# OMODRI_EtherCAT_1.net
KiCad netlist of a schematic drawn in Altium Designer
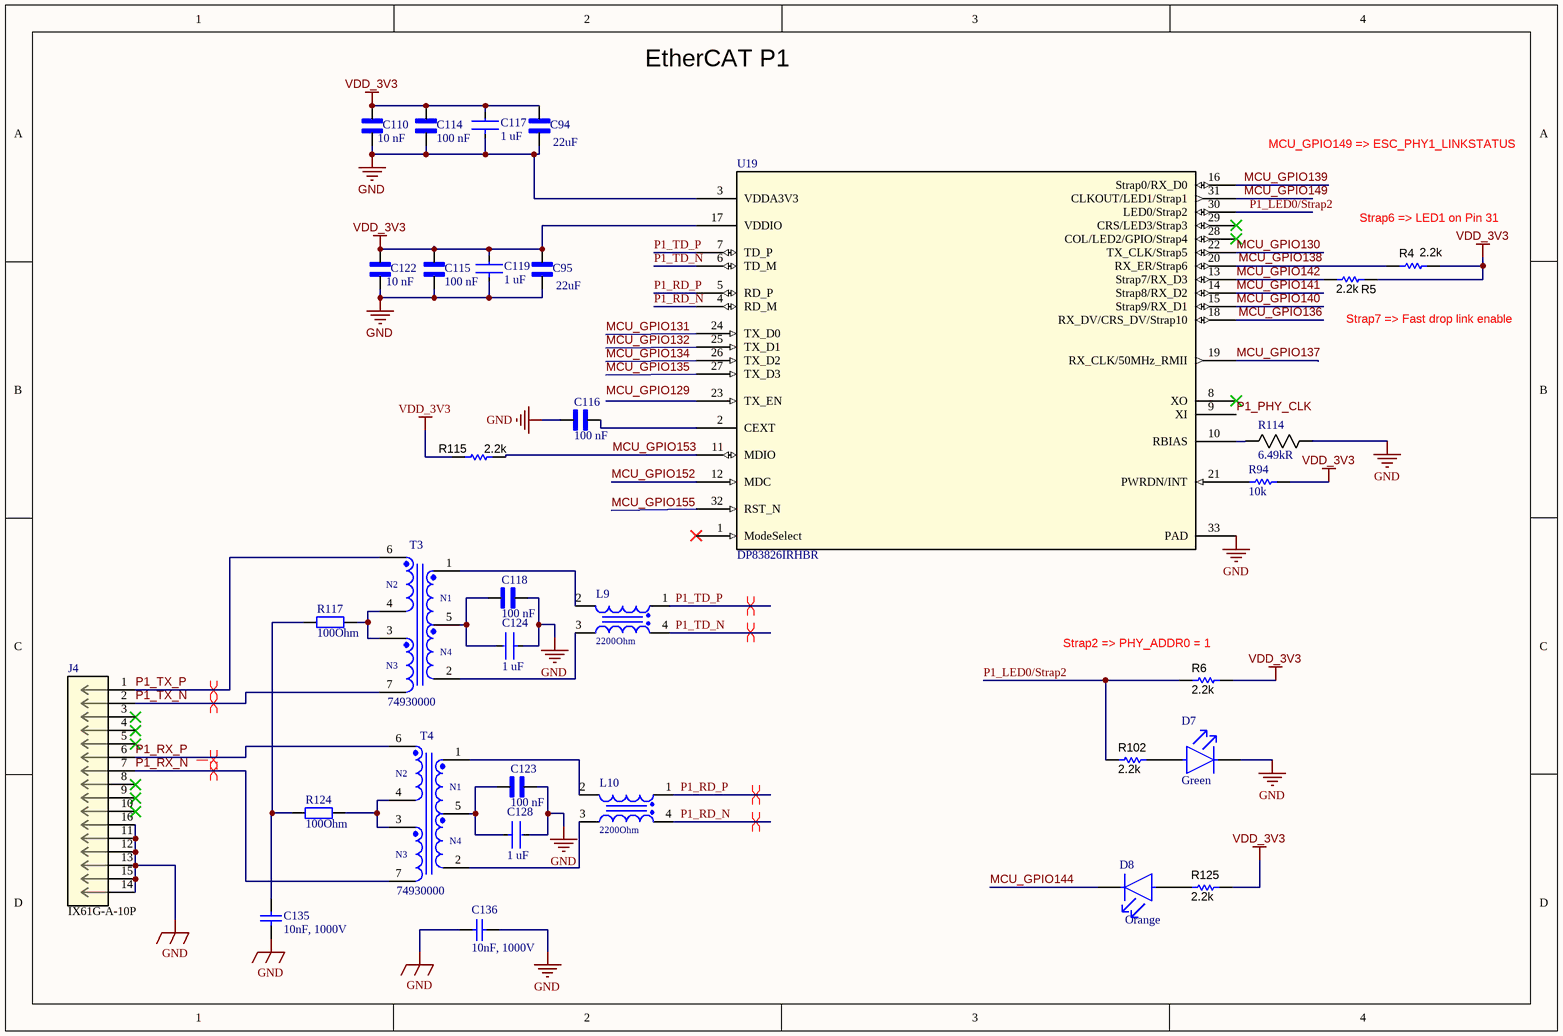
[diagram p0: OMODRI_EtherCAT_1.SchDoc]

(export (version "E")
  (design (tool "Eeschema 10.0.6"))
  (components
    (comp (ref "C94")
      (value "22uF")
      (footprint "CAPC1005X55N")
      (description "22µF ±20% 6.3V Ceramic Capacitor X5R 0402 (1005 Metric)")
      (fields (field (name "MP") "CL05A226MQ5N6J8") (field (name "MF") "Samsung Electro-Mechanics"))
      (libsource (lib "CL05A226MQ5N6J8") (part "CL05A226MQ5N6J8"))
    )
    (comp (ref "C95")
      (value "22uF")
      (footprint "CAPC1005X55N")
      (description "22µF ±20% 6.3V Ceramic Capacitor X5R 0402 (1005 Metric)")
      (fields (field (name "MP") "CL05A226MQ5N6J8") (field (name "MF") "Samsung Electro-Mechanics"))
      (libsource (lib "CL05A226MQ5N6J8") (part "CL05A226MQ5N6J8"))
    )
    (comp (ref "C110")
      (value "10 nF")
      (footprint "CAPC0603X33N")
      (description "SMD Capacitor X7R_EIA_ with Capacitance: 10000pF Tol. 10%. Rated Voltage: 25Vdc")
      (fields (field (name "MP") "GRM033R71E103KE14D") (field (name "MF") "Murata"))
      (libsource (lib "GRM033R71E103KE14D") (part "GRM033R71E103KE14D"))
    )
    (comp (ref "C114")
      (value "100 nF")
      (footprint "CAPC0603X33N")
      (description "SMD Capacitor X5R_EIA_ with Capacitance: 0.10uF Tol. 10%. Rated Voltage: 25Vdc")
      (fields (field (name "MF") "Murata") (field (name "MP") "GRM033R61E104KE14D"))
      (libsource (lib "") (part "GRM033R61E104KE14D_1"))
    )
    (comp (ref "C115")
      (value "100 nF")
      (footprint "CAPC0603X33N")
      (description "SMD Capacitor X5R_EIA_ with Capacitance: 0.10uF Tol. 10%. Rated Voltage: 25Vdc")
      (fields (field (name "MF") "Murata") (field (name "MP") "GRM033R61E104KE14D"))
      (libsource (lib "") (part "GRM033R61E104KE14D_1"))
    )
    (comp (ref "C116")
      (value "100 nF")
      (footprint "CAPC0603X33N")
      (description "SMD Capacitor X5R_EIA_ with Capacitance: 0.10uF Tol. 10%. Rated Voltage: 25Vdc")
      (fields (field (name "MF") "Murata") (field (name "MP") "GRM033R61E104KE14D"))
      (libsource (lib "GRM033R61E104KE14D") (part "GRM033R61E104KE14D"))
    )
    (comp (ref "C117")
      (value "1 uF")
      (footprint "FP-CC0201-BA-MFG")
      (description "CAP CER 1UF 6.3V X5R 0201")
      (fields (field (name "TOLERANCE") "0.2") (field (name "MANUFACTURER") "Yageo"))
      (libsource (lib "Altium Content Vault") (part "11868f565c42a9108669ba33697ecf6"))
    )
    (comp (ref "C118")
      (value "100 nF")
      (footprint "CAPC0603X33N")
      (description "SMD Capacitor X5R_EIA_ with Capacitance: 0.10uF Tol. 10%. Rated Voltage: 25Vdc")
      (fields (field (name "MF") "Murata") (field (name "MP") "GRM033R61E104KE14D"))
      (libsource (lib "GRM033R61E104KE14D") (part "GRM033R61E104KE14D"))
    )
    (comp (ref "C119")
      (value "1 uF")
      (footprint "FP-CC0201-BA-MFG")
      (description "CAP CER 1UF 6.3V X5R 0201")
      (fields (field (name "TOLERANCE") "0.2") (field (name "MANUFACTURER") "Yageo"))
      (libsource (lib "Altium Content Vault") (part "11868f565c42a9108669ba33697ecf6"))
    )
    (comp (ref "C122")
      (value "10 nF")
      (footprint "CAPC0603X33N")
      (description "SMD Capacitor X7R_EIA_ with Capacitance: 10000pF Tol. 10%. Rated Voltage: 25Vdc")
      (fields (field (name "MP") "GRM033R71E103KE14D") (field (name "MF") "Murata"))
      (libsource (lib "GRM033R71E103KE14D") (part "GRM033R71E103KE14D"))
    )
    (comp (ref "C123")
      (value "100 nF")
      (footprint "CAPC0603X33N")
      (description "SMD Capacitor X5R_EIA_ with Capacitance: 0.10uF Tol. 10%. Rated Voltage: 25Vdc")
      (fields (field (name "MF") "Murata") (field (name "MP") "GRM033R61E104KE14D"))
      (libsource (lib "GRM033R61E104KE14D") (part "GRM033R61E104KE14D"))
    )
    (comp (ref "C124")
      (value "1 uF")
      (footprint "FP-CC0201-BA-MFG")
      (description "CAP CER 1UF 6.3V X5R 0201")
      (fields (field (name "TOLERANCE") "0.2") (field (name "MANUFACTURER") "Yageo"))
      (libsource (lib "Altium Content Vault") (part "11868f565c42a9108669ba33697ecf6"))
    )
    (comp (ref "C128")
      (value "1 uF")
      (footprint "FP-CC0201-BA-MFG")
      (description "CAP CER 1UF 6.3V X5R 0201")
      (fields (field (name "TOLERANCE") "0.2") (field (name "MANUFACTURER") "Yageo"))
      (libsource (lib "Altium Content Vault") (part "11868f565c42a9108669ba33697ecf6"))
    )
    (comp (ref "C135")
      (value "10nF, 1000V")
      (footprint "WCAP-CSMH_1206_H=1.25mm")
      (description "WCAP-CSMH Ceramic Capacitors, size 1206, 10nF, 1000VDC")
      (fields (field (name "PART NUMBER") "885342208021") (field (name "PUBLISHER") "Wurth Elektronik"))
      (libsource (lib "WCAP-CSMH_1206") (part "885342208021"))
    )
    (comp (ref "C136")
      (value "10nF, 1000V")
      (footprint "WCAP-CSMH_1206_H=1.25mm")
      (description "WCAP-CSMH Ceramic Capacitors, size 1206, 10nF, 1000VDC")
      (fields (field (name "PART NUMBER") "885342208021") (field (name "PUBLISHER") "Wurth Elektronik"))
      (libsource (lib "WCAP-CSMH_1206") (part "885342208021"))
    )
    (comp (ref "D7")
      (value "SML-P11MTT86R")
      (footprint "ROHM-SML-P11MT_V")
      (description "LED Uni-Color Yellow Green 2-Pin Chip 0402(1006Metric) T/R")
      (fields
        (field (name "MANUFACTURER") "Rohm")
        (field (name "MANUFACTURER PART NUMBER") "SML-P11MTT86")
        (field (name "ILLUMINATION COLOR") "Green")
      )
      (libsource (lib "LED") (part "SML-P11MTT86R"))
    )
    (comp (ref "D8")
      (value "SML-P11DTT86R")
      (footprint "ROHM-SML-P11MT_V")
      (description "LED ORANGE CLEAR 1006 SMD")
      (fields (field (name "MANUFACTURER") "Rohm") (field (name "COLOR") "Orange"))
      (libsource (lib "LED") (part "SML-P11DTT86R"))
    )
    (comp (ref "J4")
      (value "Part Number: IX61G-A-10P")
      (footprint "CONN_1G-A-10P")
      (description "Conn Ethernet Connector RCP 10 POS Solder RA Thru-Hole 10 Terminal 1 Port Cat 5e/Cat 6a Reel")
      (fields
        (field (name "MANUFACTURER_PART_NUMBER") "IX61G-A-10P")
        (field (name "MANUFACTURER") "Hirose")
        (field (name "MANUFACTURER PART NUMBER") "IX61G-A-10P")
        (field (name "COPYRIGHT") "Copyright (C) 2018 Accelerated Designs. All rights reserved")
      )
      (libsource (lib "Hirose-iX") (part "IX61G-A-10P"))
    )
    (comp (ref "L9")
      (value "2200Ohm")
      (footprint "WE-CNSW_1206")
      (description "WE-CNSW SMT Common Mode Line Filter, size 1206, 2200Ohm, 0.2A, 50V")
      (fields
        (field (name "MANUFACTURER PART NUMBER") "744232222")
        (field (name "MANUFACTURER") "Wurth Elektronik")
      )
      (libsource (lib "WE-CNSW_1206") (part "744232222"))
    )
    (comp (ref "L10")
      (value "2200Ohm")
      (footprint "WE-CNSW_1206")
      (description "WE-CNSW SMT Common Mode Line Filter, size 1206, 2200Ohm, 0.2A, 50V")
      (fields
        (field (name "MANUFACTURER PART NUMBER") "744232222")
        (field (name "MANUFACTURER") "Wurth Elektronik")
      )
      (libsource (lib "WE-CNSW_1206") (part "744232222"))
    )
    (comp (ref "R4")
      (value "CRCW04022K20JNED")
      (footprint "0402")
      (description "RES, 2.2 k, 5%, 0.063 W, AEC-Q200 Grade 0, 0402")
      (fields (field (name "MANUFACTURER") "Vishay-Dale") (field (name "VALUEDISPLAYED") "2.2k"))
      (libsource (lib "Altium Vault - TI") (part "Resistor"))
    )
    (comp (ref "R5")
      (value "CRCW04022K20JNED")
      (footprint "0402")
      (description "RES, 2.2 k, 5%, 0.063 W, AEC-Q200 Grade 0, 0402")
      (fields (field (name "MANUFACTURER") "Vishay-Dale") (field (name "VALUEDISPLAYED") "2.2k"))
      (libsource (lib "Altium Vault - TI") (part "Resistor"))
    )
    (comp (ref "R6")
      (value "CRCW04022K20JNED")
      (footprint "0402")
      (description "RES, 2.2 k, 5%, 0.063 W, AEC-Q200 Grade 0, 0402")
      (fields (field (name "MANUFACTURER") "Vishay-Dale") (field (name "VALUEDISPLAYED") "2.2k"))
      (libsource (lib "Altium Vault - TI") (part "Resistor"))
    )
    (comp (ref "R94")
      (value "ERJ2RKF1002X")
      (footprint "RESC1005X40X25LL05T05")
      (description "Chip Resistor, 10 KOhm, +/- 1%, 0.1 W, -55 to 155 degC, 0402 (1005 Metric), RoHS, Tape and Reel")
      (fields
        (field (name "RESISTANCE") "10k")
        (field (name "TOLERANCE") "1%")
        (field (name "MANUFACTURER") "Panasonic")
      )
      (libsource (lib "Altium Content Vault") (part "RES-2"))
    )
    (comp (ref "R102")
      (value "CRCW04022K20JNED")
      (footprint "0402")
      (description "RES, 2.2 k, 5%, 0.063 W, AEC-Q200 Grade 0, 0402")
      (fields (field (name "MANUFACTURER") "Vishay-Dale") (field (name "VALUEDISPLAYED") "2.2k"))
      (libsource (lib "Altium Vault - TI") (part "Resistor"))
    )
    (comp (ref "R114")
      (value "Part Number: CRCW04026K49FKED")
      (footprint "RES_CRCW_0402")
      (description "Res Thick Film 0402 6.49K Ohm 1% 0.063W(1/16W) ±100ppm/C Pad SMD Automotive T/R")
      (fields
        (field (name "MANUFACTURER_PART_NUMBER") "CRCW04026K49FKED")
        (field (name "MANUFACTURER") "Vishay")
        (field (name "RESISTANCE") "6.49kR")
        (field (name "COPYRIGHT") "Copyright (C) 2018 Accelerated Designs. All rights reserved")
      )
      (libsource (lib "Vishay-Resistor") (part "CRCW04026K49FKED"))
    )
    (comp (ref "R115")
      (value "CRCW04022K20JNED")
      (footprint "0402")
      (description "RES, 2.2 k, 5%, 0.063 W, AEC-Q200 Grade 0, 0402")
      (fields (field (name "MANUFACTURER") "Vishay-Dale") (field (name "VALUEDISPLAYED") "2.2k"))
      (libsource (lib "Altium Vault - TI") (part "Resistor"))
    )
    (comp (ref "R117")
      (value "100Ohm")
      (footprint "WRIS-KWKB_0612_H=0.55mm")
      (description "WRIS-KWKB Thick Film Resistors, size 0612, 100Ohm, +/-5%, 0.75W")
      (fields (field (name "PART NUMBER") "561020132009") (field (name "PUBLISHER") "Wurth Elektronik"))
      (libsource (lib "561020132009_Altium_WRIS-KWKB_rev19a") (part "561020132009"))
    )
    (comp (ref "R124")
      (value "100Ohm")
      (footprint "WRIS-KWKB_0612_H=0.55mm")
      (description "WRIS-KWKB Thick Film Resistors, size 0612, 100Ohm, +/-5%, 0.75W")
      (fields (field (name "PART NUMBER") "561020132009") (field (name "PUBLISHER") "Wurth Elektronik"))
      (libsource (lib "561020132009_Altium_WRIS-KWKB_rev19a") (part "561020132009"))
    )
    (comp (ref "R125")
      (value "CRCW04022K20JNED")
      (footprint "0402")
      (description "RES, 2.2 k, 5%, 0.063 W, AEC-Q200 Grade 0, 0402")
      (fields (field (name "MANUFACTURER") "Vishay-Dale") (field (name "VALUEDISPLAYED") "2.2k"))
      (libsource (lib "Altium Vault - TI") (part "Resistor"))
    )
    (comp (ref "T3")
      (value "74930000")
      (footprint "74930000")
      (description "WE-STST Super Tiny Signal Transformer, size 4532, 350uH")
      (fields (field (name "PUBLISHER") "Wurth Elektronik"))
      (libsource (lib "WE-STST") (part "74930000"))
    )
    (comp (ref "T4")
      (value "74930000")
      (footprint "74930000")
      (description "WE-STST Super Tiny Signal Transformer, size 4532, 350uH")
      (fields (field (name "PUBLISHER") "Wurth Elektronik"))
      (libsource (lib "WE-STST") (part "74930000"))
    )
    (comp (ref "U19")
      (value "DP83826IRHBR")
      (footprint "RHB0032B")
      (fields (field (name "MANUFACTURER") "Texas Instruments"))
      (libsource (lib "TI-DP8382x") (part "DP83826IRHBR"))
    )
  )
  (nets
    (net (code "2") (name "/MCU_GPIO130") (class "Default")
      (node (ref "U19") (pin "22") (pinfunction "TX_CLK/Strap5_22") (pintype "bidirectional"))
    )
    (net (code "3") (name "/MCU_GPIO131") (class "Default")
      (node (ref "U19") (pin "24") (pinfunction "TX_D0_24") (pintype "input"))
    )
    (net (code "4") (name "/MCU_GPIO132") (class "Default")
      (node (ref "U19") (pin "25") (pinfunction "TX_D1_25") (pintype "input"))
    )
    (net (code "5") (name "/MCU_GPIO134") (class "Default")
      (node (ref "U19") (pin "26") (pinfunction "TX_D2_26") (pintype "input"))
    )
    (net (code "6") (name "/MCU_GPIO135") (class "Default")
      (node (ref "U19") (pin "27") (pinfunction "TX_D3_27") (pintype "input"))
    )
    (net (code "7") (name "/MCU_GPIO136") (class "Default")
      (node (ref "U19") (pin "18") (pinfunction "RX_DV/CRS_DV/Strap10_18") (pintype "bidirectional"))
    )
    (net (code "8") (name "/MCU_GPIO137") (class "Default")
      (node (ref "U19") (pin "19") (pinfunction "RX_CLK/50MHz_RMII_19") (pintype "output"))
    )
    (net (code "10") (name "/MCU_GPIO138") (class "Default")
      (node (ref "R4") (pin "2") (pinfunction "2_2") (pintype "passive"))
      (node (ref "U19") (pin "20") (pinfunction "RX_ER/Strap6_20") (pintype "bidirectional"))
    )
    (net (code "11") (name "/MCU_GPIO139") (class "Default")
      (node (ref "U19") (pin "16") (pinfunction "Strap0/RX_D0_16") (pintype "bidirectional"))
    )
    (net (code "12") (name "/MCU_GPIO140") (class "Default")
      (node (ref "U19") (pin "15") (pinfunction "Strap9/RX_D1_15") (pintype "bidirectional"))
    )
    (net (code "13") (name "/MCU_GPIO141") (class "Default")
      (node (ref "U19") (pin "14") (pinfunction "Strap8/RX_D2_14") (pintype "bidirectional"))
    )
    (net (code "14") (name "/MCU_GPIO142") (class "Default")
      (node (ref "R5") (pin "2") (pinfunction "2_2") (pintype "passive"))
      (node (ref "U19") (pin "13") (pinfunction "Strap7/RX_D3_13") (pintype "bidirectional"))
    )
    (net (code "15") (name "/MCU_GPIO144") (class "Default")
      (node (ref "D8") (pin "1") (pinfunction "C_1") (pintype "passive"))
    )
    (net (code "16") (name "/MCU_GPIO149") (class "Default")
      (node (ref "U19") (pin "31") (pinfunction "CLKOUT/LED1/Strap1_31") (pintype "output"))
    )
    (net (code "17") (name "/MCU_GPIO152") (class "Default")
      (node (ref "U19") (pin "12") (pinfunction "MDC_12") (pintype "input"))
    )
    (net (code "18") (name "/MCU_GPIO153") (class "Default")
      (node (ref "R115") (pin "1") (pinfunction "1_1") (pintype "passive"))
      (node (ref "U19") (pin "11") (pinfunction "MDIO_11") (pintype "bidirectional"))
    )
    (net (code "19") (name "/MCU_GPIO155") (class "Default")
      (node (ref "U19") (pin "32") (pinfunction "RST_N_32") (pintype "input"))
    )
    (net (code "20") (name "/P1_LED0{slash}Strap2") (class "Default")
      (node (ref "R102") (pin "1") (pinfunction "1_1") (pintype "passive"))
      (node (ref "R6") (pin "2") (pinfunction "2_2") (pintype "passive"))
      (node (ref "U19") (pin "30") (pinfunction "LED0/Strap2_30") (pintype "bidirectional"))
    )
    (net (code "21") (name "/P1_PHY_CLK") (class "Default")
      (node (ref "U19") (pin "9") (pinfunction "XI_9") (pintype "passive"))
    )
    (net (code "22") (name "/P1_RD_N") (class "Default")
      (node (ref "L10") (pin "4") (pinfunction "4_4") (pintype "passive"))
      (node (ref "U19") (pin "4") (pinfunction "RD_M_4") (pintype "bidirectional"))
    )
    (net (code "23") (name "/P1_RD_P") (class "Default")
      (node (ref "L10") (pin "1") (pinfunction "1_1") (pintype "passive"))
      (node (ref "U19") (pin "5") (pinfunction "RD_P_5") (pintype "bidirectional"))
    )
    (net (code "24") (name "/P1_RX_N") (class "Default")
      (node (ref "J4") (pin "7") (pinfunction "7_7") (pintype "passive"))
      (node (ref "T4") (pin "7") (pinfunction "7_7") (pintype "passive"))
    )
    (net (code "25") (name "/P1_RX_P") (class "Default")
      (node (ref "J4") (pin "6") (pinfunction "6_6") (pintype "passive"))
      (node (ref "T4") (pin "6") (pinfunction "6_6") (pintype "passive"))
    )
    (net (code "26") (name "/P1_TD_N") (class "Default")
      (node (ref "L9") (pin "4") (pinfunction "4_4") (pintype "passive"))
      (node (ref "U19") (pin "6") (pinfunction "TD_M_6") (pintype "bidirectional"))
    )
    (net (code "27") (name "/P1_TD_P") (class "Default")
      (node (ref "L9") (pin "1") (pinfunction "1_1") (pintype "passive"))
      (node (ref "U19") (pin "7") (pinfunction "TD_P_7") (pintype "bidirectional"))
    )
    (net (code "28") (name "/P1_TX_N") (class "Default")
      (node (ref "J4") (pin "2") (pinfunction "2_2") (pintype "passive"))
      (node (ref "T3") (pin "7") (pinfunction "7_7") (pintype "passive"))
    )
    (net (code "29") (name "/P1_TX_P") (class "Default")
      (node (ref "J4") (pin "1") (pinfunction "1_1") (pintype "passive"))
      (node (ref "T3") (pin "6") (pinfunction "6_6") (pintype "passive"))
    )
    (net (code "30") (name "GND") (class "Default")
      (node (ref "C110") (pin "1") (pinfunction "1_1") (pintype "passive"))
      (node (ref "C114") (pin "2") (pinfunction "2_2") (pintype "passive"))
      (node (ref "C115") (pin "2") (pinfunction "2_2") (pintype "passive"))
      (node (ref "C116") (pin "2") (pinfunction "2_2") (pintype "passive"))
      (node (ref "C117") (pin "1") (pinfunction "1_1") (pintype "passive"))
      (node (ref "C118") (pin "1") (pinfunction "1_1") (pintype "passive"))
      (node (ref "C119") (pin "1") (pinfunction "1_1") (pintype "passive"))
      (node (ref "C122") (pin "1") (pinfunction "1_1") (pintype "passive"))
      (node (ref "C123") (pin "1") (pinfunction "1_1") (pintype "passive"))
      (node (ref "C124") (pin "1") (pinfunction "1_1") (pintype "passive"))
      (node (ref "C128") (pin "2") (pinfunction "2_2") (pintype "passive"))
      (node (ref "C135") (pin "1") (pinfunction "1_1") (pintype "passive"))
      (node (ref "C136") (pin "1") (pinfunction "1_1") (pintype "passive"))
      (node (ref "C136") (pin "2") (pinfunction "2_2") (pintype "passive"))
      (node (ref "C94") (pin "1") (pinfunction "1_1") (pintype "passive"))
      (node (ref "C95") (pin "1") (pinfunction "1_1") (pintype "passive"))
      (node (ref "D7") (pin "1") (pinfunction "C_1") (pintype "passive"))
      (node (ref "J4") (pin "11") (pinfunction "11_11") (pintype "passive"))
      (node (ref "J4") (pin "12") (pinfunction "12_12") (pintype "passive"))
      (node (ref "J4") (pin "13") (pinfunction "13_13") (pintype "passive"))
      (node (ref "J4") (pin "14") (pinfunction "14_14") (pintype "passive"))
      (node (ref "J4") (pin "15") (pinfunction "15_15") (pintype "passive"))
      (node (ref "J4") (pin "16") (pinfunction "16_16") (pintype "passive"))
      (node (ref "R114") (pin "1") (pinfunction "1_1") (pintype "passive"))
      (node (ref "U19") (pin "3") (pinfunction "VDDA3V3_3") (pintype "power_in"))
      (node (ref "U19") (pin "33") (pinfunction "PAD_33") (pintype "power_in"))
    )
    (net (code "31") (name "Net-(C118-Pad2)") (class "Default")
      (node (ref "C118") (pin "2") (pinfunction "2_2") (pintype "passive"))
      (node (ref "C124") (pin "2") (pinfunction "2_2") (pintype "passive"))
      (node (ref "T3") (pin "5") (pinfunction "5_5") (pintype "passive"))
    )
    (net (code "32") (name "Net-(C123-Pad2)") (class "Default")
      (node (ref "C123") (pin "2") (pinfunction "2_2") (pintype "passive"))
      (node (ref "C128") (pin "1") (pinfunction "1_1") (pintype "passive"))
      (node (ref "T4") (pin "5") (pinfunction "5_5") (pintype "passive"))
    )
    (net (code "33") (name "Net-(C135-Pad2)") (class "Default")
      (node (ref "C135") (pin "2") (pinfunction "2_2") (pintype "passive"))
      (node (ref "R117") (pin "1") (pinfunction "1_1") (pintype "passive"))
      (node (ref "R124") (pin "1") (pinfunction "1_1") (pintype "passive"))
    )
    (net (code "34") (name "Net-(D7-A)") (class "Default")
      (node (ref "D7") (pin "2") (pinfunction "A_2") (pintype "passive"))
      (node (ref "R102") (pin "2") (pinfunction "2_2") (pintype "passive"))
    )
    (net (code "35") (name "Net-(D8-A)") (class "Default")
      (node (ref "D8") (pin "2") (pinfunction "A_2") (pintype "passive"))
      (node (ref "R125") (pin "2") (pinfunction "2_2") (pintype "passive"))
    )
    (net (code "36") (name "Net-(L9-Pad2)") (class "Default")
      (node (ref "L9") (pin "2") (pinfunction "2_2") (pintype "passive"))
      (node (ref "T3") (pin "1") (pinfunction "1_1") (pintype "passive"))
    )
    (net (code "37") (name "Net-(L9-Pad3)") (class "Default")
      (node (ref "L9") (pin "3") (pinfunction "3_3") (pintype "passive"))
      (node (ref "T3") (pin "2") (pinfunction "2_2") (pintype "passive"))
    )
    (net (code "38") (name "Net-(L10-Pad2)") (class "Default")
      (node (ref "L10") (pin "2") (pinfunction "2_2") (pintype "passive"))
      (node (ref "T4") (pin "1") (pinfunction "1_1") (pintype "passive"))
    )
    (net (code "39") (name "Net-(L10-Pad3)") (class "Default")
      (node (ref "L10") (pin "3") (pinfunction "3_3") (pintype "passive"))
      (node (ref "T4") (pin "2") (pinfunction "2_2") (pintype "passive"))
    )
    (net (code "40") (name "Net-(R117-Pad2)") (class "Default")
      (node (ref "R117") (pin "2") (pinfunction "2_2") (pintype "passive"))
      (node (ref "T3") (pin "3") (pinfunction "3_3") (pintype "passive"))
      (node (ref "T3") (pin "4") (pinfunction "4_4") (pintype "passive"))
    )
    (net (code "41") (name "Net-(R124-Pad2)") (class "Default")
      (node (ref "R124") (pin "2") (pinfunction "2_2") (pintype "passive"))
      (node (ref "T4") (pin "3") (pinfunction "3_3") (pintype "passive"))
      (node (ref "T4") (pin "4") (pinfunction "4_4") (pintype "passive"))
    )
    (net (code "42") (name "Net-(U19-CEXT)") (class "Default")
      (node (ref "C116") (pin "1") (pinfunction "1_1") (pintype "passive"))
      (node (ref "U19") (pin "2") (pinfunction "CEXT_2") (pintype "passive"))
    )
    (net (code "43") (name "Net-(U19-PWRDN{slash}INT)") (class "Default")
      (node (ref "R94") (pin "2") (pinfunction "2_2") (pintype "passive"))
      (node (ref "U19") (pin "21") (pinfunction "PWRDN/INT_21") (pintype "input"))
    )
    (net (code "44") (name "Net-(U19-RBIAS)") (class "Default")
      (node (ref "R114") (pin "2") (pinfunction "2_2") (pintype "passive"))
      (node (ref "U19") (pin "10") (pinfunction "RBIAS_10") (pintype "passive"))
    )
    (net (code "45") (name "VDD_3V3") (class "Default")
      (node (ref "C110") (pin "2") (pinfunction "2_2") (pintype "passive"))
      (node (ref "C114") (pin "1") (pinfunction "1_1") (pintype "passive"))
      (node (ref "C115") (pin "1") (pinfunction "1_1") (pintype "passive"))
      (node (ref "C117") (pin "2") (pinfunction "2_2") (pintype "passive"))
      (node (ref "C119") (pin "2") (pinfunction "2_2") (pintype "passive"))
      (node (ref "C122") (pin "2") (pinfunction "2_2") (pintype "passive"))
      (node (ref "C94") (pin "2") (pinfunction "2_2") (pintype "passive"))
      (node (ref "C95") (pin "2") (pinfunction "2_2") (pintype "passive"))
      (node (ref "R115") (pin "2") (pinfunction "2_2") (pintype "passive"))
      (node (ref "R125") (pin "1") (pinfunction "1_1") (pintype "passive"))
      (node (ref "R4") (pin "1") (pinfunction "1_1") (pintype "passive"))
      (node (ref "R5") (pin "1") (pinfunction "1_1") (pintype "passive"))
      (node (ref "R6") (pin "1") (pinfunction "1_1") (pintype "passive"))
      (node (ref "R94") (pin "1") (pinfunction "1_1") (pintype "passive"))
      (node (ref "U19") (pin "17") (pinfunction "VDDIO_17") (pintype "power_in"))
    )
    (net (code "46") (name "unconnected-(J4-Pad3)") (class "Default")
      (node (ref "J4") (pin "3") (pinfunction "3_3") (pintype "passive+no_connect"))
    )
    (net (code "47") (name "unconnected-(J4-Pad4)") (class "Default")
      (node (ref "J4") (pin "4") (pinfunction "4_4") (pintype "passive+no_connect"))
    )
    (net (code "48") (name "unconnected-(J4-Pad5)") (class "Default")
      (node (ref "J4") (pin "5") (pinfunction "5_5") (pintype "passive+no_connect"))
    )
    (net (code "49") (name "unconnected-(J4-Pad8)") (class "Default")
      (node (ref "J4") (pin "8") (pinfunction "8_8") (pintype "passive+no_connect"))
    )
    (net (code "50") (name "unconnected-(J4-Pad9)") (class "Default")
      (node (ref "J4") (pin "9") (pinfunction "9_9") (pintype "passive+no_connect"))
    )
    (net (code "51") (name "unconnected-(J4-Pad10)") (class "Default")
      (node (ref "J4") (pin "10") (pinfunction "10_10") (pintype "passive+no_connect"))
    )
    (net (code "52") (name "unconnected-(U19-COL{slash}LED2{slash}GPIO{slash}Strap4-Pad28)") (class "Default")
      (node (ref "U19") (pin "28") (pinfunction "COL/LED2/GPIO/Strap4_28") (pintype "bidirectional+no_connect"))
    )
    (net (code "53") (name "unconnected-(U19-CRS{slash}LED3{slash}Strap3-Pad29)") (class "Default")
      (node (ref "U19") (pin "29") (pinfunction "CRS/LED3/Strap3_29") (pintype "bidirectional+no_connect"))
    )
    (net (code "54") (name "unconnected-(U19-ModeSelect-Pad1)") (class "Default")
      (node (ref "U19") (pin "1") (pinfunction "ModeSelect_1") (pintype "input+no_connect"))
    )
    (net (code "55") (name "unconnected-(U19-TX_EN-Pad23)") (class "Default")
      (node (ref "U19") (pin "23") (pinfunction "TX_EN_23") (pintype "input"))
    )
    (net (code "56") (name "unconnected-(U19-XO-Pad8)") (class "Default")
      (node (ref "U19") (pin "8") (pinfunction "XO_8") (pintype "passive+no_connect"))
    )
  )
)
